# FTDI.net
KiCad netlist of a schematic drawn in Altium Designer
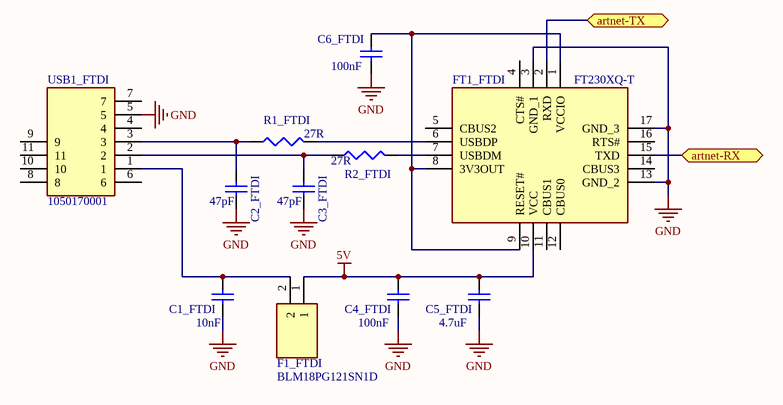
[diagram p0: FTDI.SchDoc]

(export (version "E")
  (design (tool "Eeschema 10.0.6"))
  (components
    (comp (ref "C1_FTDI")
      (value "10nF")
      (footprint "1608[0603]")
      (description "Capacitor (Semiconductor SIM Model)")
      (fields (field (name "Comment") "Cap Semi") (field (name "PUBLISHER") "Altium Limited"))
      (libsource (lib "Miscellaneous Devices") (part "Cap Semi"))
    )
    (comp (ref "C2_FTDI")
      (value "47pF")
      (footprint "1608[0603]")
      (description "Capacitor (Semiconductor SIM Model)")
      (fields (field (name "Comment") "Cap Semi") (field (name "PUBLISHER") "Altium Limited"))
      (libsource (lib "Miscellaneous Devices") (part "Cap Semi"))
    )
    (comp (ref "C3_FTDI")
      (value "47pF")
      (footprint "1608[0603]")
      (description "Capacitor (Semiconductor SIM Model)")
      (fields (field (name "Comment") "Cap Semi") (field (name "PUBLISHER") "Altium Limited"))
      (libsource (lib "Miscellaneous Devices") (part "Cap Semi"))
    )
    (comp (ref "C4_FTDI")
      (value "100nF")
      (footprint "1608[0603]")
      (description "Capacitor (Semiconductor SIM Model)")
      (fields (field (name "Comment") "Cap Semi") (field (name "PUBLISHER") "Altium Limited"))
      (libsource (lib "Miscellaneous Devices") (part "Cap Semi"))
    )
    (comp (ref "C5_FTDI")
      (value "4.7uF")
      (footprint "1608[0603]")
      (description "Capacitor (Semiconductor SIM Model)")
      (fields (field (name "Comment") "Cap Semi") (field (name "PUBLISHER") "Altium Limited"))
      (libsource (lib "Miscellaneous Devices") (part "Cap Semi"))
    )
    (comp (ref "C6_FTDI")
      (value "100nF")
      (footprint "1608[0603]")
      (description "Capacitor (Semiconductor SIM Model)")
      (fields (field (name "Comment") "Cap Semi") (field (name "PUBLISHER") "Altium Limited"))
      (libsource (lib "Miscellaneous Devices") (part "Cap Semi"))
    )
    (comp (ref "F1_FTDI")
      (value "BLM18PG121SN1D")
      (footprint "LX1-Teensy:BEADC1608X95N")
      (description "Filter")
      (fields
        (field (name "MOUSER PART NUMBER") "81-BLM18PG121SN1D")
        (field (name "RS PART NUMBER") "7241380P")
      )
      (libsource (lib "LX1-Teensy") (part "BLM18PG121SN1D"))
    )
    (comp (ref "FT1_FTDI")
      (value "FT230XQ-T")
      (footprint "LX1-FTDI:QFN65P400X400X80-17N")
      (description "Integrated Circuit")
      (fields (field (name "MOUSER PART NUMBER") "895-FT230XQ-T") (field (name "RS PART NUMBER") "8888716"))
      (libsource (lib "LX1-FTDI") (part "FT230XQ-T"))
    )
    (comp (ref "R1_FTDI")
      (value "27R")
      (footprint "J1-0603")
      (description "Resistor")
      (fields (field (name "Comment") "Res3") (field (name "PUBLISHER") "Altium Limited"))
      (libsource (lib "Miscellaneous Devices") (part "Res3"))
    )
    (comp (ref "R2_FTDI")
      (value "27R")
      (footprint "J1-0603")
      (description "Resistor")
      (fields (field (name "Comment") "Res3") (field (name "PUBLISHER") "Altium Limited"))
      (libsource (lib "Miscellaneous Devices") (part "Res3"))
    )
    (comp (ref "USB1_FTDI")
      (value "1050170001")
      (footprint "LX1-Teensy:MICROUSB-BTYPE")
      (description "Connector")
      (libsource (lib "LX1-Teensy") (part "1050170001"))
    )
  )
  (nets
    (net (code "1") (name "/artnet-RX") (class "Default")
      (node (ref "FT1_FTDI") (pin "15") (pinfunction "TXD_15") (pintype "passive"))
    )
    (net (code "2") (name "/artnet-TX") (class "Default")
      (node (ref "FT1_FTDI") (pin "2") (pinfunction "RXD_2") (pintype "passive"))
    )
    (net (code "3") (name "5V") (class "Default")
      (node (ref "C4_FTDI") (pin "2") (pinfunction "2_2") (pintype "passive"))
      (node (ref "C5_FTDI") (pin "2") (pinfunction "2_2") (pintype "passive"))
      (node (ref "F1_FTDI") (pin "1") (pinfunction "1_1") (pintype "passive"))
      (node (ref "FT1_FTDI") (pin "10") (pinfunction "VCC_10") (pintype "passive"))
    )
    (net (code "4") (name "GND") (class "Default")
      (node (ref "C1_FTDI") (pin "1") (pinfunction "1_1") (pintype "passive"))
      (node (ref "C2_FTDI") (pin "1") (pinfunction "1_1") (pintype "passive"))
      (node (ref "C3_FTDI") (pin "1") (pinfunction "1_1") (pintype "passive"))
      (node (ref "C4_FTDI") (pin "1") (pinfunction "1_1") (pintype "passive"))
      (node (ref "C5_FTDI") (pin "1") (pinfunction "1_1") (pintype "passive"))
      (node (ref "C6_FTDI") (pin "2") (pinfunction "2_2") (pintype "passive"))
      (node (ref "FT1_FTDI") (pin "13") (pinfunction "GND_2_13") (pintype "passive"))
      (node (ref "FT1_FTDI") (pin "17") (pinfunction "GND_3_17") (pintype "passive"))
      (node (ref "FT1_FTDI") (pin "3") (pinfunction "GND_1_3") (pintype "passive"))
      (node (ref "USB1_FTDI") (pin "5") (pinfunction "5_5") (pintype "passive"))
    )
    (net (code "5") (name "Net-(C1_FTDI-Pad2)") (class "Default")
      (node (ref "C1_FTDI") (pin "2") (pinfunction "2_2") (pintype "passive"))
      (node (ref "F1_FTDI") (pin "2") (pinfunction "2_2") (pintype "passive"))
      (node (ref "USB1_FTDI") (pin "1") (pinfunction "1_1") (pintype "passive"))
    )
    (net (code "6") (name "Net-(C2_FTDI-Pad2)") (class "Default")
      (node (ref "C2_FTDI") (pin "2") (pinfunction "2_2") (pintype "passive"))
      (node (ref "R1_FTDI") (pin "1") (pinfunction "1_1") (pintype "passive"))
      (node (ref "USB1_FTDI") (pin "3") (pinfunction "3_3") (pintype "passive"))
    )
    (net (code "7") (name "Net-(C3_FTDI-Pad2)") (class "Default")
      (node (ref "C3_FTDI") (pin "2") (pinfunction "2_2") (pintype "passive"))
      (node (ref "R2_FTDI") (pin "1") (pinfunction "1_1") (pintype "passive"))
      (node (ref "USB1_FTDI") (pin "2") (pinfunction "2_2") (pintype "passive"))
    )
    (net (code "8") (name "Net-(FT1_FTDI-3V3OUT)") (class "Default")
      (node (ref "C6_FTDI") (pin "1") (pinfunction "1_1") (pintype "passive"))
      (node (ref "FT1_FTDI") (pin "1") (pinfunction "VCCIO_1") (pintype "passive"))
      (node (ref "FT1_FTDI") (pin "8") (pinfunction "3V3OUT_8") (pintype "passive"))
      (node (ref "FT1_FTDI") (pin "9") (pinfunction "RESET#_9") (pintype "passive"))
    )
    (net (code "9") (name "Net-(FT1_FTDI-USBDM)") (class "Default")
      (node (ref "FT1_FTDI") (pin "7") (pinfunction "USBDM_7") (pintype "passive"))
      (node (ref "R2_FTDI") (pin "2") (pinfunction "2_2") (pintype "passive"))
    )
    (net (code "10") (name "Net-(FT1_FTDI-USBDP)") (class "Default")
      (node (ref "FT1_FTDI") (pin "6") (pinfunction "USBDP_6") (pintype "passive"))
      (node (ref "R1_FTDI") (pin "2") (pinfunction "2_2") (pintype "passive"))
    )
    (net (code "11") (name "unconnected-(FT1_FTDI-CBUS0-Pad12)") (class "Default")
      (node (ref "FT1_FTDI") (pin "12") (pinfunction "CBUS0_12") (pintype "passive"))
    )
    (net (code "12") (name "unconnected-(FT1_FTDI-CBUS1-Pad11)") (class "Default")
      (node (ref "FT1_FTDI") (pin "11") (pinfunction "CBUS1_11") (pintype "passive"))
    )
    (net (code "13") (name "unconnected-(FT1_FTDI-CBUS2-Pad5)") (class "Default")
      (node (ref "FT1_FTDI") (pin "5") (pinfunction "CBUS2_5") (pintype "passive"))
    )
    (net (code "14") (name "unconnected-(FT1_FTDI-CBUS3-Pad14)") (class "Default")
      (node (ref "FT1_FTDI") (pin "14") (pinfunction "CBUS3_14") (pintype "passive"))
    )
    (net (code "15") (name "unconnected-(FT1_FTDI-CTS#-Pad4)") (class "Default")
      (node (ref "FT1_FTDI") (pin "4") (pinfunction "CTS#_4") (pintype "passive"))
    )
    (net (code "16") (name "unconnected-(FT1_FTDI-RTS#-Pad16)") (class "Default")
      (node (ref "FT1_FTDI") (pin "16") (pinfunction "RTS#_16") (pintype "passive"))
    )
    (net (code "17") (name "unconnected-(USB1_FTDI-Pad4)") (class "Default")
      (node (ref "USB1_FTDI") (pin "4") (pinfunction "4_4") (pintype "passive"))
    )
    (net (code "18") (name "unconnected-(USB1_FTDI-Pad6)") (class "Default")
      (node (ref "USB1_FTDI") (pin "6") (pinfunction "6_6") (pintype "passive"))
    )
    (net (code "19") (name "unconnected-(USB1_FTDI-Pad7)") (class "Default")
      (node (ref "USB1_FTDI") (pin "7") (pinfunction "7_7") (pintype "passive"))
    )
    (net (code "20") (name "unconnected-(USB1_FTDI-Pad8)") (class "Default")
      (node (ref "USB1_FTDI") (pin "8") (pinfunction "8_8") (pintype "passive"))
    )
    (net (code "21") (name "unconnected-(USB1_FTDI-Pad9)") (class "Default")
      (node (ref "USB1_FTDI") (pin "9") (pinfunction "9_9") (pintype "passive"))
    )
    (net (code "22") (name "unconnected-(USB1_FTDI-Pad10)") (class "Default")
      (node (ref "USB1_FTDI") (pin "10") (pinfunction "10_10") (pintype "passive"))
    )
    (net (code "23") (name "unconnected-(USB1_FTDI-Pad11)") (class "Default")
      (node (ref "USB1_FTDI") (pin "11") (pinfunction "11_11") (pintype "passive"))
    )
  )
)
